# X-Bot.net
KiCad netlist of a schematic drawn in Altium Designer
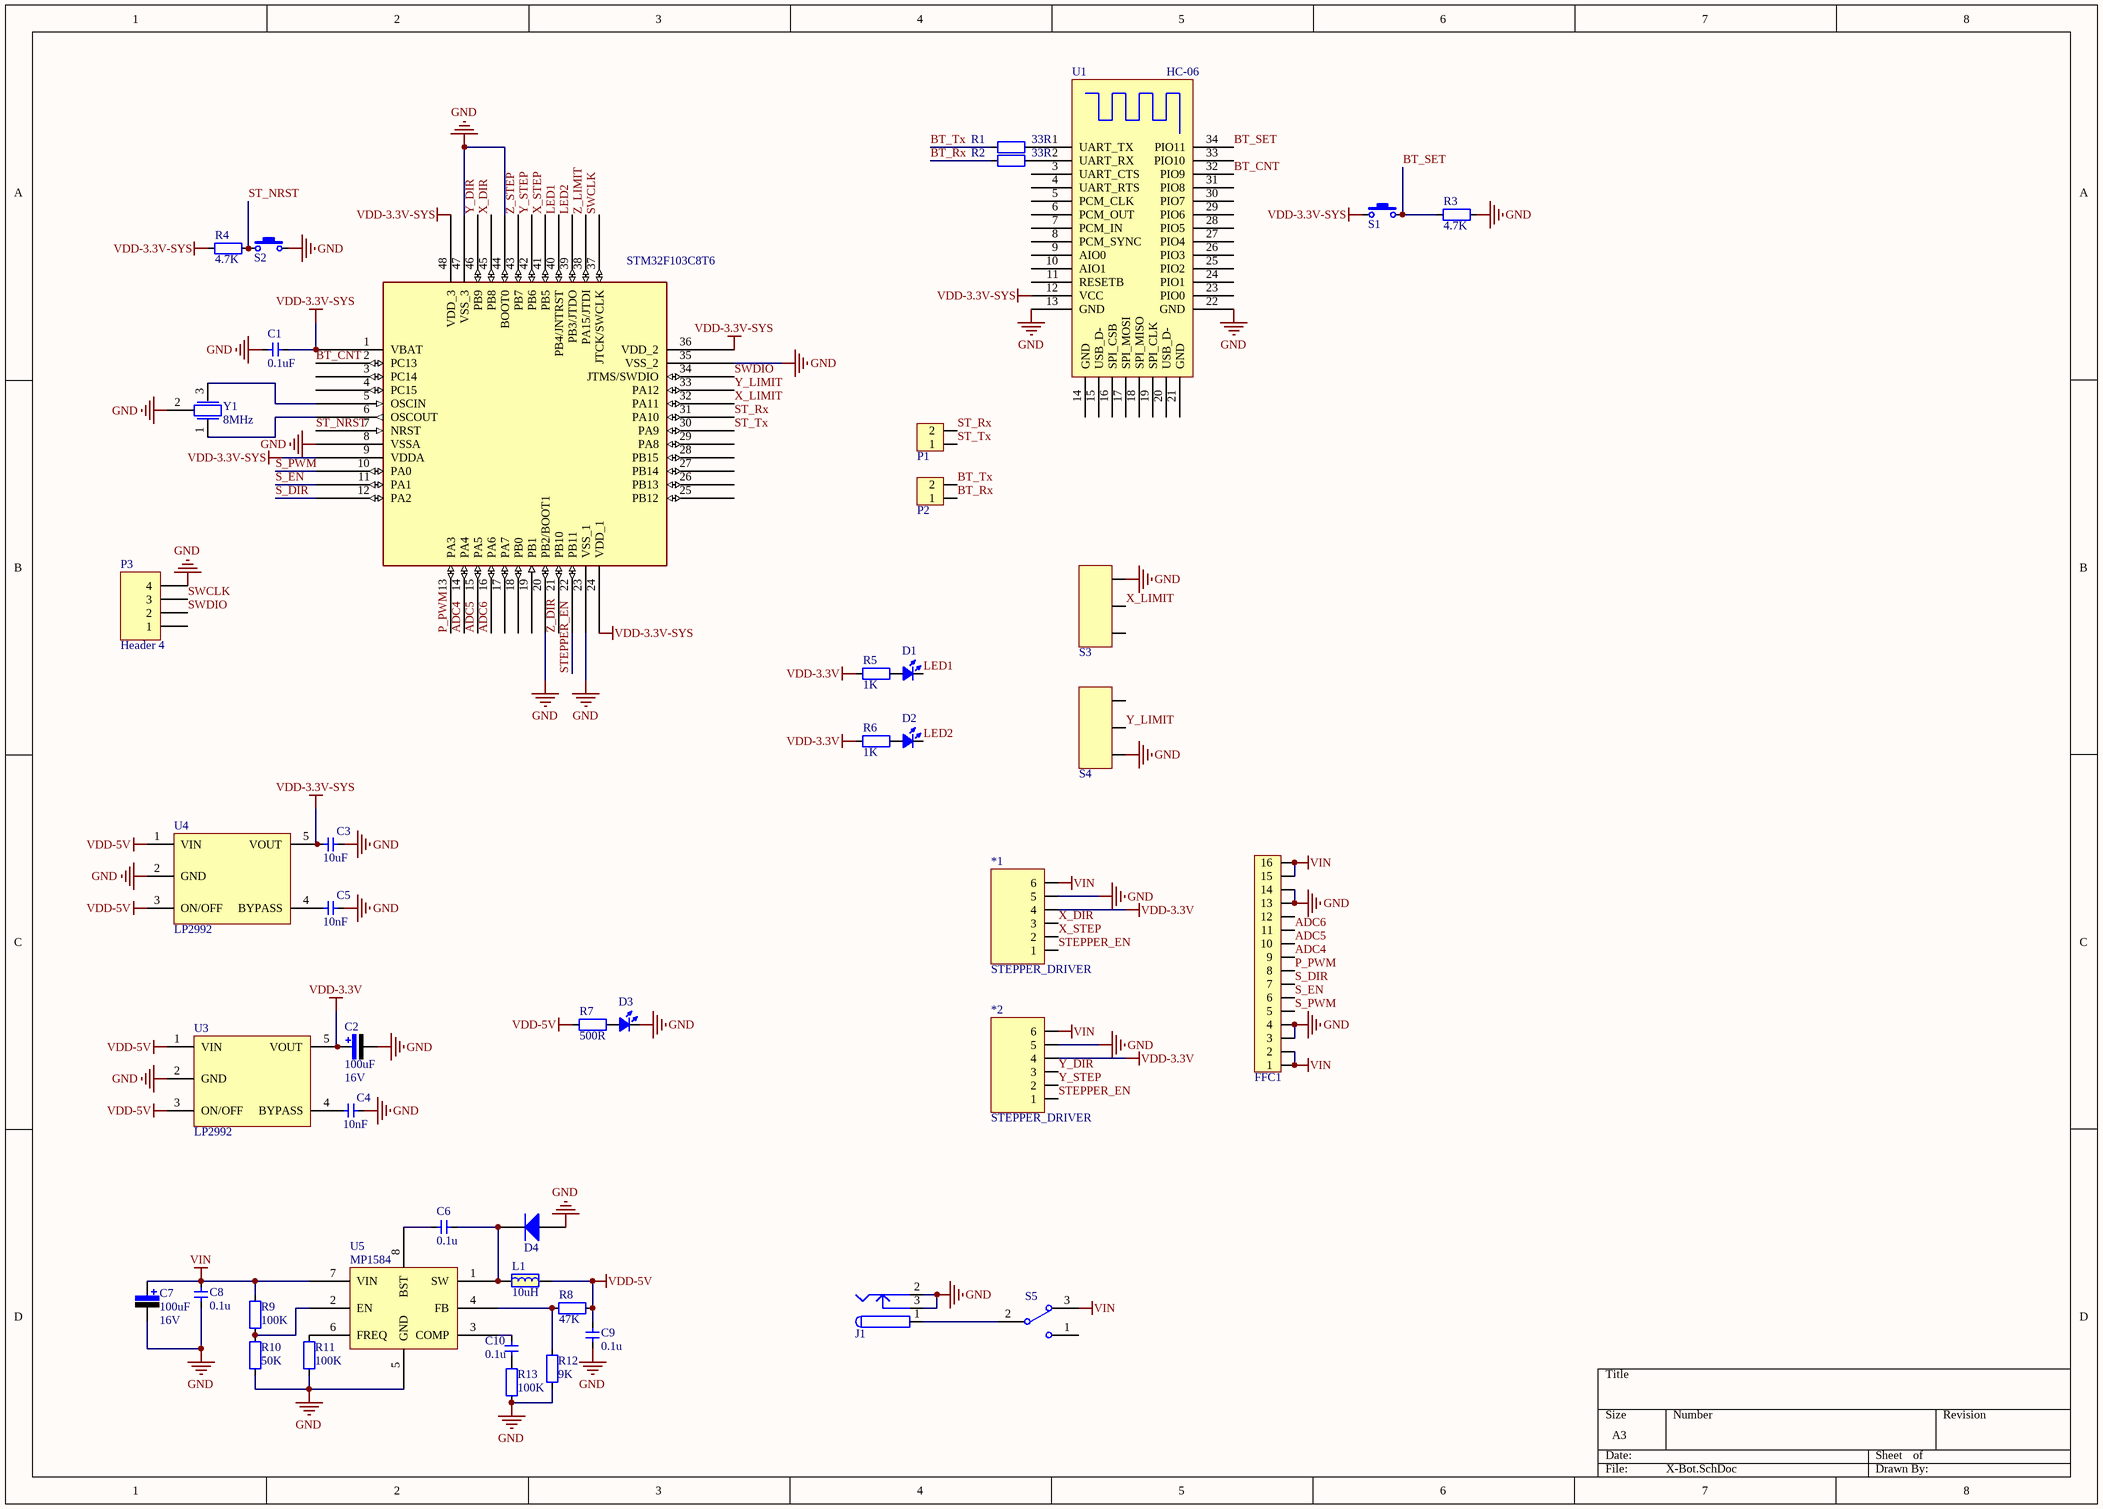
[diagram p0: X-Bot.SchDoc]

(export (version "E")
  (design (tool "Eeschema 10.0.6"))
  (components
    (comp (ref "*1")
      (value "STEPPER_DRIVER")
      (footprint "STEPPER_DRIVER")
      (libsource (lib "mLib") (part "STEPPER_DRIVER"))
    )
    (comp (ref "*2")
      (value "STEPPER_DRIVER")
      (footprint "STEPPER_DRIVER")
      (libsource (lib "mLib") (part "STEPPER_DRIVER"))
    )
    (comp (ref "C1")
      (value "0.1uF")
      (footprint "mLib:0603-CAP")
      (description "Capacitor")
      (libsource (lib "mLib") (part "电容-0603"))
    )
    (comp (ref "C2")
      (value "100uF")
      (footprint "3528-CAP")
      (description "极性电解电容")
      (fields
        (field (name "VOL") "16V")
        (field (name "Comment") "电容 3528")
        (field (name "PUBLISHER") "Altium Limited")
      )
      (libsource (lib "") (part "电容 3528_1"))
    )
    (comp (ref "C3")
      (value "10uF")
      (footprint "mLib:0603-CAP")
      (description "Capacitor")
      (fields (field (name "Comment") "10nF"))
      (libsource (lib "mLib") (part "电容-0603"))
    )
    (comp (ref "C4")
      (value "10nF")
      (footprint "mLib:0603-CAP")
      (description "Capacitor")
      (libsource (lib "mLib") (part "电容-0603"))
    )
    (comp (ref "C5")
      (value "10nF")
      (footprint "mLib:0603-CAP")
      (description "Capacitor")
      (libsource (lib "mLib") (part "电容-0603"))
    )
    (comp (ref "C6")
      (value "0.1u")
      (footprint "mLib:0603-CAP")
      (description "Capacitor")
      (fields (field (name "Comment") "电容-0603"))
      (libsource (lib "mLib") (part "电容-0603"))
    )
    (comp (ref "C7")
      (value "100uF")
      (footprint "3528-CAP")
      (description "极性电解电容")
      (fields
        (field (name "VOL") "16V")
        (field (name "Comment") "电容 3528")
        (field (name "PUBLISHER") "Altium Limited")
      )
      (libsource (lib "mLib") (part "电容 3528"))
    )
    (comp (ref "C8")
      (value "0.1u")
      (footprint "mLib:0603-CAP")
      (description "Capacitor")
      (fields (field (name "Comment") "电容-0603"))
      (libsource (lib "mLib") (part "电容-0603"))
    )
    (comp (ref "C9")
      (value "0.1u")
      (footprint "mLib:0603-CAP")
      (description "Capacitor")
      (fields (field (name "Comment") "电容-0603"))
      (libsource (lib "mLib") (part "电容-0603"))
    )
    (comp (ref "C10")
      (value "0.1u")
      (footprint "mLib:0603-CAP")
      (description "Capacitor")
      (fields (field (name "Comment") "电容-0603"))
      (libsource (lib "mLib") (part "电容-0603"))
    )
    (comp (ref "D1")
      (value "LED-0603")
      (footprint "mLib:0603-LED-BLUE")
      (description "LED")
      (libsource (lib "mLib") (part "LED-0603"))
    )
    (comp (ref "D2")
      (value "LED-0603")
      (footprint "mLib:0603-LED-BLUE")
      (description "LED")
      (libsource (lib "mLib") (part "LED-0603"))
    )
    (comp (ref "D3")
      (value "LED-0603")
      (footprint "mLib:0603-LED-BLUE")
      (description "LED")
      (libsource (lib "mLib") (part "LED-0603"))
    )
    (comp (ref "D4")
      (value "二极管-5819W")
      (footprint "SOD-123")
      (description "40V")
      (libsource (lib "mLib") (part "二极管-5819W"))
    )
    (comp (ref "FFC1")
      (value "FFC_0.5_16")
      (footprint "FFC_0.5_16")
      (description "FFC")
      (libsource (lib "Integrated_Library") (part "FFC_0.5_16"))
    )
    (comp (ref "J1")
      (value "PowerJack_2.5")
      (footprint "KLD_0202")
      (description "DC Power Jack")
      (libsource (lib "Integrated_Library") (part "PowerJack_2.5"))
    )
    (comp (ref "L1")
      (value "10uH")
      (footprint "L-SMD-7")
      (description "磁珠")
      (libsource (lib "mLib") (part "电感-0805"))
    )
    (comp (ref "P1")
      (value "HDR1x2_2.54")
      (footprint "HDR1X2_2.54_180")
      (description "Header")
      (libsource (lib "Integrated_Library") (part "HDR1x2_2.54"))
    )
    (comp (ref "P2")
      (value "HDR1x2_2.54")
      (footprint "HDR1X2_2.54_180")
      (description "Header")
      (libsource (lib "Integrated_Library") (part "HDR1x2_2.54"))
    )
    (comp (ref "P3")
      (value "Header 4")
      (footprint "HDR1X4")
      (description "Header, 4-Pin")
      (fields (field (name "PUBLISHER") "Altium Limited"))
      (libsource (lib "Miscellaneous Connectors") (part "Header 4"))
    )
    (comp (ref "R1")
      (value "33R")
      (footprint "mLib:0603-RES")
      (description "Resistor")
      (fields (field (name "Comment") "500R"))
      (libsource (lib "") (part "电阻-0603_2"))
    )
    (comp (ref "R2")
      (value "33R")
      (footprint "mLib:0603-RES")
      (description "Resistor")
      (fields (field (name "Comment") "500R"))
      (libsource (lib "") (part "电阻-0603_2"))
    )
    (comp (ref "R3")
      (value "4.7K")
      (footprint "mLib:0603-RES")
      (description "Resistor")
      (libsource (lib "mLib") (part "电阻-0603"))
    )
    (comp (ref "R4")
      (value "4.7K")
      (footprint "mLib:0603-RES")
      (description "Resistor")
      (libsource (lib "mLib") (part "电阻-0603"))
    )
    (comp (ref "R5")
      (value "1K")
      (footprint "mLib:0603-RES")
      (description "Resistor")
      (fields (field (name "Comment") "500R"))
      (libsource (lib "") (part "电阻-0603_2"))
    )
    (comp (ref "R6")
      (value "1K")
      (footprint "mLib:0603-RES")
      (description "Resistor")
      (fields (field (name "Comment") "500R"))
      (libsource (lib "") (part "电阻-0603_2"))
    )
    (comp (ref "R7")
      (value "500R")
      (footprint "mLib:0603-RES")
      (description "Resistor")
      (libsource (lib "") (part "电阻-0603_2"))
    )
    (comp (ref "R8")
      (value "47K")
      (footprint "mLib:0603-RES")
      (description "Resistor")
      (fields (field (name "Comment") "100K"))
      (libsource (lib "mLib") (part "电阻-0603"))
    )
    (comp (ref "R9")
      (value "100K")
      (footprint "mLib:0603-RES")
      (description "Resistor")
      (libsource (lib "") (part "电阻-0603_1"))
    )
    (comp (ref "R10")
      (value "50K")
      (footprint "mLib:0603-RES")
      (description "Resistor")
      (fields (field (name "Comment") "100K"))
      (libsource (lib "") (part "电阻-0603_1"))
    )
    (comp (ref "R11")
      (value "100K")
      (footprint "mLib:0603-RES")
      (description "Resistor")
      (libsource (lib "") (part "电阻-0603_1"))
    )
    (comp (ref "R12")
      (value "9K")
      (footprint "mLib:0603-RES")
      (description "Resistor")
      (fields (field (name "Comment") "100K"))
      (libsource (lib "") (part "电阻-0603_1"))
    )
    (comp (ref "R13")
      (value "100K")
      (footprint "mLib:0603-RES")
      (description "Resistor")
      (libsource (lib "") (part "电阻-0603_1"))
    )
    (comp (ref "S1")
      (value "ButtonTACT_3x4x2_180")
      (footprint "ButtonTACT_3x4x2_180H")
      (description "Button")
      (libsource (lib "Integrated_Library") (part "ButtonTACT_3x4x2_180"))
    )
    (comp (ref "S2")
      (value "ButtonTACT_3x4x2_180")
      (footprint "ButtonTACT_3x4x2_180H")
      (description "Button")
      (libsource (lib "Integrated_Library") (part "ButtonTACT_3x4x2_180"))
    )
    (comp (ref "S3")
      (value "LimitSwitch")
      (footprint "Limit Switch")
      (libsource (lib "mLib") (part "LimitSwitch"))
    )
    (comp (ref "S4")
      (value "LimitSwitch")
      (footprint "Limit Switch")
      (libsource (lib "mLib") (part "LimitSwitch"))
    )
    (comp (ref "S5")
      (value "SwitchSPDT_4.3x8.6_D90")
      (footprint "SwitchSPDT_4.3X8.6_D90")
      (description "Switch")
      (libsource (lib "Integrated_Library") (part "SwitchSPDT_4.3x8.6_D90"))
    )
    (comp (ref "U1")
      (value "HC-06")
      (footprint "蓝牙模块HC-06")
      (description "HM bluetooth module HM-01,HM-02,HM-09")
      (libsource (lib "HMSoft") (part "HM01_02_09_1"))
    )
    (comp (ref "U2")
      (value "STM32F103C8T6")
      (footprint "LQFP-48")
      (description "MCU")
      (libsource (lib "mLib") (part "STM32F103C8T6"))
    )
    (comp (ref "U3")
      (value "LP2992")
      (footprint "SOT23-5")
      (description "LDO")
      (libsource (lib "mLib") (part "LP2992"))
    )
    (comp (ref "U4")
      (value "LP2992")
      (footprint "SOT23-5")
      (description "LDO")
      (libsource (lib "mLib") (part "LP2992"))
    )
    (comp (ref "U5")
      (value "MP1584")
      (footprint "SO-8")
      (description "电源芯片")
      (libsource (lib "mLib") (part "MP1584"))
    )
    (comp (ref "Y1")
      (value "8MHz")
      (footprint "晶振-3P")
      (description "村田贴片")
      (libsource (lib "mLib") (part "晶振-3Pin"))
    )
  )
  (nets
    (net (code "1") (name "/ADC4") (class "Default")
      (node (ref "FFC1") (pin "9") (pinfunction "9_9") (pintype "passive"))
      (node (ref "U2") (pin "14") (pinfunction "PA4_14") (pintype "bidirectional"))
    )
    (net (code "2") (name "/ADC5") (class "Default")
      (node (ref "FFC1") (pin "10") (pinfunction "10_10") (pintype "passive"))
      (node (ref "U2") (pin "15") (pinfunction "PA5_15") (pintype "bidirectional"))
    )
    (net (code "3") (name "/ADC6") (class "Default")
      (node (ref "FFC1") (pin "11") (pinfunction "11_11") (pintype "passive"))
      (node (ref "U2") (pin "16") (pinfunction "PA6_16") (pintype "bidirectional"))
    )
    (net (code "4") (name "/BT_CNT") (class "Default")
      (node (ref "U1") (pin "32") (pinfunction "PIO9_32") (pintype "passive"))
      (node (ref "U2") (pin "2") (pinfunction "PC13_2") (pintype "bidirectional"))
    )
    (net (code "5") (name "/BT_Rx") (class "Default")
      (node (ref "P2") (pin "1") (pinfunction "1_1") (pintype "passive"))
      (node (ref "R2") (pin "1") (pinfunction "1_1") (pintype "passive"))
    )
    (net (code "6") (name "/BT_SET") (class "Default")
      (node (ref "R3") (pin "2") (pinfunction "2_2") (pintype "passive"))
      (node (ref "S1") (pin "2") (pinfunction "2_2") (pintype "passive"))
      (node (ref "U1") (pin "34") (pinfunction "PIO11_34") (pintype "passive"))
    )
    (net (code "7") (name "/BT_Tx") (class "Default")
      (node (ref "P2") (pin "2") (pinfunction "2_2") (pintype "passive"))
      (node (ref "R1") (pin "1") (pinfunction "1_1") (pintype "passive"))
    )
    (net (code "8") (name "/LED1") (class "Default")
      (node (ref "D1") (pin "2") (pinfunction "K_2") (pintype "passive"))
      (node (ref "U2") (pin "40") (pinfunction "PB4/JNTRST_40") (pintype "bidirectional"))
    )
    (net (code "9") (name "/LED2") (class "Default")
      (node (ref "D2") (pin "2") (pinfunction "K_2") (pintype "passive"))
      (node (ref "U2") (pin "39") (pinfunction "PB3/JTDO_39") (pintype "bidirectional"))
    )
    (net (code "10") (name "/P_PWM") (class "Default")
      (node (ref "FFC1") (pin "8") (pinfunction "8_8") (pintype "passive"))
      (node (ref "U2") (pin "13") (pinfunction "PA3_13") (pintype "bidirectional"))
    )
    (net (code "11") (name "/STEPPER_EN") (class "Default")
      (node (ref "*1") (pin "1") (pinfunction "1_1") (pintype "passive"))
      (node (ref "*2") (pin "1") (pinfunction "1_1") (pintype "passive"))
      (node (ref "U2") (pin "22") (pinfunction "PB11_22") (pintype "bidirectional"))
    )
    (net (code "12") (name "/ST_NRST") (class "Default")
      (node (ref "R4") (pin "1") (pinfunction "1_1") (pintype "passive"))
      (node (ref "S2") (pin "1") (pinfunction "1_1") (pintype "passive"))
      (node (ref "U2") (pin "7") (pinfunction "NRST_7") (pintype "input"))
    )
    (net (code "13") (name "/ST_Rx") (class "Default")
      (node (ref "P1") (pin "2") (pinfunction "2_2") (pintype "passive"))
      (node (ref "U2") (pin "31") (pinfunction "PA10_31") (pintype "bidirectional"))
    )
    (net (code "14") (name "/ST_Tx") (class "Default")
      (node (ref "P1") (pin "1") (pinfunction "1_1") (pintype "passive"))
      (node (ref "U2") (pin "30") (pinfunction "PA9_30") (pintype "bidirectional"))
    )
    (net (code "15") (name "/SWCLK") (class "Default")
      (node (ref "P3") (pin "3") (pinfunction "3_3") (pintype "passive"))
      (node (ref "U2") (pin "37") (pinfunction "JTCK/SWCLK_37") (pintype "bidirectional"))
    )
    (net (code "16") (name "/SWDIO") (class "Default")
      (node (ref "P3") (pin "2") (pinfunction "2_2") (pintype "passive"))
      (node (ref "U2") (pin "34") (pinfunction "JTMS/SWDIO_34") (pintype "bidirectional"))
    )
    (net (code "17") (name "/S_DIR") (class "Default")
      (node (ref "FFC1") (pin "7") (pinfunction "7_7") (pintype "passive"))
      (node (ref "U2") (pin "12") (pinfunction "PA2_12") (pintype "bidirectional"))
    )
    (net (code "18") (name "/S_EN") (class "Default")
      (node (ref "FFC1") (pin "6") (pinfunction "6_6") (pintype "passive"))
      (node (ref "U2") (pin "11") (pinfunction "PA1_11") (pintype "bidirectional"))
    )
    (net (code "19") (name "/S_PWM") (class "Default")
      (node (ref "FFC1") (pin "5") (pinfunction "5_5") (pintype "passive"))
      (node (ref "U2") (pin "10") (pinfunction "PA0_10") (pintype "bidirectional"))
    )
    (net (code "20") (name "/X_DIR") (class "Default")
      (node (ref "*1") (pin "3") (pinfunction "3_3") (pintype "passive"))
      (node (ref "U2") (pin "45") (pinfunction "PB8_45") (pintype "bidirectional"))
    )
    (net (code "21") (name "/X_LIMIT") (class "Default")
      (node (ref "S3") (pin "2") (pintype "power_in"))
      (node (ref "U2") (pin "32") (pinfunction "PA11_32") (pintype "bidirectional"))
    )
    (net (code "22") (name "/X_STEP") (class "Default")
      (node (ref "*1") (pin "2") (pinfunction "2_2") (pintype "passive"))
      (node (ref "U2") (pin "41") (pinfunction "PB5_41") (pintype "bidirectional"))
    )
    (net (code "23") (name "/Y_DIR") (class "Default")
      (node (ref "*2") (pin "3") (pinfunction "3_3") (pintype "passive"))
      (node (ref "U2") (pin "46") (pinfunction "PB9_46") (pintype "bidirectional"))
    )
    (net (code "24") (name "/Y_LIMIT") (class "Default")
      (node (ref "S4") (pin "2") (pintype "power_in"))
      (node (ref "U2") (pin "33") (pinfunction "PA12_33") (pintype "bidirectional"))
    )
    (net (code "25") (name "/Y_STEP") (class "Default")
      (node (ref "*2") (pin "2") (pinfunction "2_2") (pintype "passive"))
      (node (ref "U2") (pin "42") (pinfunction "PB6_42") (pintype "bidirectional"))
    )
    (net (code "26") (name "/Z_DIR") (class "Default")
      (node (ref "U2") (pin "21") (pinfunction "PB10_21") (pintype "bidirectional"))
    )
    (net (code "27") (name "/Z_LIMIT") (class "Default")
      (node (ref "U2") (pin "38") (pinfunction "PA15/JTDI_38") (pintype "bidirectional"))
    )
    (net (code "28") (name "/Z_STEP") (class "Default")
      (node (ref "U2") (pin "43") (pinfunction "PB7_43") (pintype "bidirectional"))
    )
    (net (code "29") (name "GND") (class "Default")
      (node (ref "*1") (pin "5") (pinfunction "5_5") (pintype "passive"))
      (node (ref "*2") (pin "5") (pinfunction "5_5") (pintype "passive"))
      (node (ref "C1") (pin "1") (pinfunction "1_1") (pintype "passive"))
      (node (ref "C2") (pin "2") (pinfunction "2_2") (pintype "passive"))
      (node (ref "C3") (pin "1") (pinfunction "1_1") (pintype "passive"))
      (node (ref "C4") (pin "1") (pinfunction "1_1") (pintype "passive"))
      (node (ref "C5") (pin "1") (pinfunction "1_1") (pintype "passive"))
      (node (ref "C7") (pin "2") (pinfunction "2_2") (pintype "passive"))
      (node (ref "C8") (pin "1") (pinfunction "1_1") (pintype "passive"))
      (node (ref "C9") (pin "2") (pinfunction "2_2") (pintype "passive"))
      (node (ref "D3") (pin "2") (pinfunction "K_2") (pintype "passive"))
      (node (ref "D4") (pin "1") (pinfunction "A_1") (pintype "passive"))
      (node (ref "FFC1") (pin "13") (pinfunction "13_13") (pintype "passive"))
      (node (ref "FFC1") (pin "14") (pinfunction "14_14") (pintype "passive"))
      (node (ref "FFC1") (pin "3") (pinfunction "3_3") (pintype "passive"))
      (node (ref "FFC1") (pin "4") (pinfunction "4_4") (pintype "passive"))
      (node (ref "J1") (pin "2") (pinfunction "2_2") (pintype "power_in"))
      (node (ref "J1") (pin "3") (pinfunction "3_3") (pintype "power_in"))
      (node (ref "P3") (pin "4") (pinfunction "4_4") (pintype "passive"))
      (node (ref "R10") (pin "1") (pinfunction "1_1") (pintype "passive"))
      (node (ref "R11") (pin "1") (pinfunction "1_1") (pintype "passive"))
      (node (ref "R12") (pin "1") (pinfunction "1_1") (pintype "passive"))
      (node (ref "R13") (pin "1") (pinfunction "1_1") (pintype "passive"))
      (node (ref "R3") (pin "1") (pinfunction "1_1") (pintype "passive"))
      (node (ref "S2") (pin "2") (pinfunction "2_2") (pintype "passive"))
      (node (ref "S3") (pin "3") (pintype "power_in"))
      (node (ref "S4") (pin "1") (pintype "power_in"))
      (node (ref "U1") (pin "13") (pinfunction "GND_13") (pintype "passive"))
      (node (ref "U1") (pin "22") (pinfunction "GND_22") (pintype "passive"))
      (node (ref "U2") (pin "20") (pinfunction "PB2/BOOT1_20") (pintype "bidirectional"))
      (node (ref "U2") (pin "23") (pinfunction "VSS_1_23") (pintype "power_in"))
      (node (ref "U2") (pin "35") (pinfunction "VSS_2_35") (pintype "power_in"))
      (node (ref "U2") (pin "44") (pinfunction "BOOT0_44") (pintype "bidirectional"))
      (node (ref "U2") (pin "47") (pinfunction "VSS_3_47") (pintype "power_in"))
      (node (ref "U2") (pin "8") (pinfunction "VSSA_8") (pintype "power_in"))
      (node (ref "U3") (pin "2") (pinfunction "GND_2") (pintype "passive"))
      (node (ref "U4") (pin "2") (pinfunction "GND_2") (pintype "passive"))
      (node (ref "U5") (pin "5") (pinfunction "GND_5") (pintype "passive"))
      (node (ref "Y1") (pin "2") (pinfunction "2_2") (pintype "passive"))
    )
    (net (code "30") (name "Net-(C10-Pad1)") (class "Default")
      (node (ref "C10") (pin "1") (pinfunction "1_1") (pintype "passive"))
      (node (ref "R13") (pin "2") (pinfunction "2_2") (pintype "passive"))
    )
    (net (code "31") (name "Net-(D1-A)") (class "Default")
      (node (ref "D1") (pin "1") (pinfunction "A_1") (pintype "passive"))
      (node (ref "R5") (pin "2") (pinfunction "2_2") (pintype "passive"))
    )
    (net (code "32") (name "Net-(D2-A)") (class "Default")
      (node (ref "D2") (pin "1") (pinfunction "A_1") (pintype "passive"))
      (node (ref "R6") (pin "2") (pinfunction "2_2") (pintype "passive"))
    )
    (net (code "33") (name "Net-(D3-A)") (class "Default")
      (node (ref "D3") (pin "1") (pinfunction "A_1") (pintype "passive"))
      (node (ref "R7") (pin "2") (pinfunction "2_2") (pintype "passive"))
    )
    (net (code "34") (name "Net-(D4-K)") (class "Default")
      (node (ref "C6") (pin "2") (pinfunction "2_2") (pintype "passive"))
      (node (ref "D4") (pin "2") (pinfunction "K_2") (pintype "passive"))
      (node (ref "L1") (pin "1") (pintype "passive"))
      (node (ref "U5") (pin "1") (pinfunction "SW_1") (pintype "passive"))
    )
    (net (code "35") (name "Net-(J1-Pad1)") (class "Default")
      (node (ref "J1") (pin "1") (pinfunction "1_1") (pintype "power_in"))
      (node (ref "S5") (pin "2") (pinfunction "2_2") (pintype "passive"))
    )
    (net (code "36") (name "Net-(U1-UART_RX)") (class "Default")
      (node (ref "R2") (pin "2") (pinfunction "2_2") (pintype "passive"))
      (node (ref "U1") (pin "2") (pinfunction "UART_RX_2") (pintype "passive"))
    )
    (net (code "37") (name "Net-(U1-UART_TX)") (class "Default")
      (node (ref "R1") (pin "2") (pinfunction "2_2") (pintype "passive"))
      (node (ref "U1") (pin "1") (pinfunction "UART_TX_1") (pintype "passive"))
    )
    (net (code "38") (name "Net-(U2-OSCIN)") (class "Default")
      (node (ref "U2") (pin "5") (pinfunction "OSCIN_5") (pintype "input"))
      (node (ref "Y1") (pin "3") (pinfunction "3_3") (pintype "passive"))
    )
    (net (code "39") (name "Net-(U2-OSCOUT)") (class "Default")
      (node (ref "U2") (pin "6") (pinfunction "OSCOUT_6") (pintype "output"))
      (node (ref "Y1") (pin "1") (pinfunction "1_1") (pintype "passive"))
    )
    (net (code "40") (name "Net-(U3-BYPASS)") (class "Default")
      (node (ref "C4") (pin "2") (pinfunction "2_2") (pintype "passive"))
      (node (ref "U3") (pin "4") (pinfunction "BYPASS_4") (pintype "passive"))
    )
    (net (code "41") (name "Net-(U4-BYPASS)") (class "Default")
      (node (ref "C5") (pin "2") (pinfunction "2_2") (pintype "passive"))
      (node (ref "U4") (pin "4") (pinfunction "BYPASS_4") (pintype "passive"))
    )
    (net (code "42") (name "Net-(U5-BST)") (class "Default")
      (node (ref "C6") (pin "1") (pinfunction "1_1") (pintype "passive"))
      (node (ref "U5") (pin "8") (pinfunction "BST_8") (pintype "passive"))
    )
    (net (code "43") (name "Net-(U5-COMP)") (class "Default")
      (node (ref "C10") (pin "2") (pinfunction "2_2") (pintype "passive"))
      (node (ref "U5") (pin "3") (pinfunction "COMP_3") (pintype "passive"))
    )
    (net (code "44") (name "Net-(U5-EN)") (class "Default")
      (node (ref "R10") (pin "2") (pinfunction "2_2") (pintype "passive"))
      (node (ref "R9") (pin "1") (pinfunction "1_1") (pintype "passive"))
      (node (ref "U5") (pin "2") (pinfunction "EN_2") (pintype "passive"))
    )
    (net (code "45") (name "Net-(U5-FB)") (class "Default")
      (node (ref "R12") (pin "2") (pinfunction "2_2") (pintype "passive"))
      (node (ref "R8") (pin "2") (pinfunction "2_2") (pintype "passive"))
      (node (ref "U5") (pin "4") (pinfunction "FB_4") (pintype "passive"))
    )
    (net (code "46") (name "Net-(U5-FREQ)") (class "Default")
      (node (ref "R11") (pin "2") (pinfunction "2_2") (pintype "passive"))
      (node (ref "U5") (pin "6") (pinfunction "FREQ_6") (pintype "passive"))
    )
    (net (code "47") (name "VDD-3.3V") (class "Default")
      (node (ref "*1") (pin "4") (pinfunction "4_4") (pintype "passive"))
      (node (ref "*2") (pin "4") (pinfunction "4_4") (pintype "passive"))
      (node (ref "C2") (pin "1") (pinfunction "1_1") (pintype "passive"))
      (node (ref "R5") (pin "1") (pinfunction "1_1") (pintype "passive"))
      (node (ref "R6") (pin "1") (pinfunction "1_1") (pintype "passive"))
      (node (ref "U3") (pin "5") (pinfunction "VOUT_5") (pintype "passive"))
    )
    (net (code "48") (name "VDD-3.3V-SYS") (class "Default")
      (node (ref "C1") (pin "2") (pinfunction "2_2") (pintype "passive"))
      (node (ref "C3") (pin "2") (pinfunction "2_2") (pintype "passive"))
      (node (ref "R4") (pin "2") (pinfunction "2_2") (pintype "passive"))
      (node (ref "S1") (pin "1") (pinfunction "1_1") (pintype "passive"))
      (node (ref "U1") (pin "12") (pinfunction "VCC_12") (pintype "passive"))
      (node (ref "U2") (pin "1") (pinfunction "VBAT_1") (pintype "power_in"))
      (node (ref "U2") (pin "24") (pinfunction "VDD_1_24") (pintype "power_in"))
      (node (ref "U2") (pin "36") (pinfunction "VDD_2_36") (pintype "power_in"))
      (node (ref "U2") (pin "48") (pinfunction "VDD_3_48") (pintype "power_in"))
      (node (ref "U2") (pin "9") (pinfunction "VDDA_9") (pintype "power_in"))
      (node (ref "U4") (pin "5") (pinfunction "VOUT_5") (pintype "passive"))
    )
    (net (code "49") (name "VDD-5V") (class "Default")
      (node (ref "C9") (pin "1") (pinfunction "1_1") (pintype "passive"))
      (node (ref "L1") (pin "2") (pinfunction "2_2") (pintype "passive"))
      (node (ref "R7") (pin "1") (pinfunction "1_1") (pintype "passive"))
      (node (ref "R8") (pin "1") (pinfunction "1_1") (pintype "passive"))
      (node (ref "U3") (pin "1") (pinfunction "VIN_1") (pintype "passive"))
      (node (ref "U3") (pin "3") (pinfunction "ON/OFF_3") (pintype "passive"))
      (node (ref "U4") (pin "1") (pinfunction "VIN_1") (pintype "passive"))
      (node (ref "U4") (pin "3") (pinfunction "ON/OFF_3") (pintype "passive"))
    )
    (net (code "50") (name "VIN") (class "Default")
      (node (ref "*1") (pin "6") (pinfunction "6_6") (pintype "passive"))
      (node (ref "*2") (pin "6") (pinfunction "6_6") (pintype "passive"))
      (node (ref "C7") (pin "1") (pinfunction "1_1") (pintype "passive"))
      (node (ref "C8") (pin "2") (pinfunction "2_2") (pintype "passive"))
      (node (ref "FFC1") (pin "1") (pinfunction "1_1") (pintype "passive"))
      (node (ref "FFC1") (pin "15") (pinfunction "15_15") (pintype "passive"))
      (node (ref "FFC1") (pin "16") (pinfunction "16_16") (pintype "passive"))
      (node (ref "FFC1") (pin "2") (pinfunction "2_2") (pintype "passive"))
      (node (ref "R9") (pin "2") (pinfunction "2_2") (pintype "passive"))
      (node (ref "S5") (pin "3") (pinfunction "3_3") (pintype "passive"))
      (node (ref "U5") (pin "7") (pinfunction "VIN_7") (pintype "passive"))
    )
    (net (code "51") (name "unconnected-(FFC1-Pad12)") (class "Default")
      (node (ref "FFC1") (pin "12") (pinfunction "12_12") (pintype "passive"))
    )
    (net (code "52") (name "unconnected-(P3-Pad1)") (class "Default")
      (node (ref "P3") (pin "1") (pinfunction "1_1") (pintype "passive"))
    )
    (net (code "53") (name "unconnected-(S3-Pad1)") (class "Default")
      (node (ref "S3") (pin "1") (pintype "power_in"))
    )
    (net (code "54") (name "unconnected-(S4-Pad3)") (class "Default")
      (node (ref "S4") (pin "3") (pintype "power_in"))
    )
    (net (code "55") (name "unconnected-(S5-Pad1)") (class "Default")
      (node (ref "S5") (pin "1") (pinfunction "1_1") (pintype "passive"))
    )
    (net (code "56") (name "unconnected-(U1-AIO0-Pad9)") (class "Default")
      (node (ref "U1") (pin "9") (pinfunction "AIO0_9") (pintype "passive"))
    )
    (net (code "57") (name "unconnected-(U1-AIO1-Pad10)") (class "Default")
      (node (ref "U1") (pin "10") (pinfunction "AIO1_10") (pintype "passive"))
    )
    (net (code "58") (name "unconnected-(U1-GND-Pad14)") (class "Default")
      (node (ref "U1") (pin "14") (pinfunction "GND_14") (pintype "passive"))
    )
    (net (code "59") (name "unconnected-(U1-GND-Pad21)") (class "Default")
      (node (ref "U1") (pin "21") (pinfunction "GND_21") (pintype "passive"))
    )
    (net (code "60") (name "unconnected-(U1-PCM_CLK-Pad5)") (class "Default")
      (node (ref "U1") (pin "5") (pinfunction "PCM_CLK_5") (pintype "passive"))
    )
    (net (code "61") (name "unconnected-(U1-PCM_IN-Pad7)") (class "Default")
      (node (ref "U1") (pin "7") (pinfunction "PCM_IN_7") (pintype "passive"))
    )
    (net (code "62") (name "unconnected-(U1-PCM_OUT-Pad6)") (class "Default")
      (node (ref "U1") (pin "6") (pinfunction "PCM_OUT_6") (pintype "passive"))
    )
    (net (code "63") (name "unconnected-(U1-PCM_SYNC-Pad8)") (class "Default")
      (node (ref "U1") (pin "8") (pinfunction "PCM_SYNC_8") (pintype "passive"))
    )
    (net (code "64") (name "unconnected-(U1-PIO0-Pad23)") (class "Default")
      (node (ref "U1") (pin "23") (pinfunction "PIO0_23") (pintype "passive"))
    )
    (net (code "65") (name "unconnected-(U1-PIO1-Pad24)") (class "Default")
      (node (ref "U1") (pin "24") (pinfunction "PIO1_24") (pintype "passive"))
    )
    (net (code "66") (name "unconnected-(U1-PIO2-Pad25)") (class "Default")
      (node (ref "U1") (pin "25") (pinfunction "PIO2_25") (pintype "passive"))
    )
    (net (code "67") (name "unconnected-(U1-PIO3-Pad26)") (class "Default")
      (node (ref "U1") (pin "26") (pinfunction "PIO3_26") (pintype "passive"))
    )
    (net (code "68") (name "unconnected-(U1-PIO4-Pad27)") (class "Default")
      (node (ref "U1") (pin "27") (pinfunction "PIO4_27") (pintype "passive"))
    )
    (net (code "69") (name "unconnected-(U1-PIO5-Pad28)") (class "Default")
      (node (ref "U1") (pin "28") (pinfunction "PIO5_28") (pintype "passive"))
    )
    (net (code "70") (name "unconnected-(U1-PIO6-Pad29)") (class "Default")
      (node (ref "U1") (pin "29") (pinfunction "PIO6_29") (pintype "passive"))
    )
    (net (code "71") (name "unconnected-(U1-PIO7-Pad30)") (class "Default")
      (node (ref "U1") (pin "30") (pinfunction "PIO7_30") (pintype "passive"))
    )
    (net (code "72") (name "unconnected-(U1-PIO8-Pad31)") (class "Default")
      (node (ref "U1") (pin "31") (pinfunction "PIO8_31") (pintype "passive"))
    )
    (net (code "73") (name "unconnected-(U1-PIO10-Pad33)") (class "Default")
      (node (ref "U1") (pin "33") (pinfunction "PIO10_33") (pintype "passive"))
    )
    (net (code "74") (name "unconnected-(U1-RESETB-Pad11)") (class "Default")
      (node (ref "U1") (pin "11") (pinfunction "RESETB_11") (pintype "passive"))
    )
    (net (code "75") (name "unconnected-(U1-SPI_CLK-Pad19)") (class "Default")
      (node (ref "U1") (pin "19") (pinfunction "SPI_CLK_19") (pintype "passive"))
    )
    (net (code "76") (name "unconnected-(U1-SPI_CSB-Pad16)") (class "Default")
      (node (ref "U1") (pin "16") (pinfunction "SPI_CSB_16") (pintype "passive"))
    )
    (net (code "77") (name "unconnected-(U1-SPI_MISO-Pad18)") (class "Default")
      (node (ref "U1") (pin "18") (pinfunction "SPI_MISO_18") (pintype "passive"))
    )
    (net (code "78") (name "unconnected-(U1-SPI_MOSI-Pad17)") (class "Default")
      (node (ref "U1") (pin "17") (pinfunction "SPI_MOSI_17") (pintype "passive"))
    )
    (net (code "79") (name "unconnected-(U1-UART_CTS-Pad3)") (class "Default")
      (node (ref "U1") (pin "3") (pinfunction "UART_CTS_3") (pintype "passive"))
    )
    (net (code "80") (name "unconnected-(U1-UART_RTS-Pad4)") (class "Default")
      (node (ref "U1") (pin "4") (pinfunction "UART_RTS_4") (pintype "passive"))
    )
    (net (code "81") (name "unconnected-(U1-USB_D--Pad15)") (class "Default")
      (node (ref "U1") (pin "15") (pinfunction "USB_D-_15") (pintype "passive"))
    )
    (net (code "82") (name "unconnected-(U1-USB_D--Pad20)") (class "Default")
      (node (ref "U1") (pin "20") (pinfunction "USB_D-_20") (pintype "passive"))
    )
    (net (code "83") (name "unconnected-(U2-PA7-Pad17)") (class "Default")
      (node (ref "U2") (pin "17") (pinfunction "PA7_17") (pintype "bidirectional"))
    )
    (net (code "84") (name "unconnected-(U2-PA8-Pad29)") (class "Default")
      (node (ref "U2") (pin "29") (pinfunction "PA8_29") (pintype "bidirectional"))
    )
    (net (code "85") (name "unconnected-(U2-PB0-Pad18)") (class "Default")
      (node (ref "U2") (pin "18") (pinfunction "PB0_18") (pintype "bidirectional"))
    )
    (net (code "86") (name "unconnected-(U2-PB1-Pad19)") (class "Default")
      (node (ref "U2") (pin "19") (pinfunction "PB1_19") (pintype "input"))
    )
    (net (code "87") (name "unconnected-(U2-PB12-Pad25)") (class "Default")
      (node (ref "U2") (pin "25") (pinfunction "PB12_25") (pintype "bidirectional"))
    )
    (net (code "88") (name "unconnected-(U2-PB13-Pad26)") (class "Default")
      (node (ref "U2") (pin "26") (pinfunction "PB13_26") (pintype "bidirectional"))
    )
    (net (code "89") (name "unconnected-(U2-PB14-Pad27)") (class "Default")
      (node (ref "U2") (pin "27") (pinfunction "PB14_27") (pintype "bidirectional"))
    )
    (net (code "90") (name "unconnected-(U2-PB15-Pad28)") (class "Default")
      (node (ref "U2") (pin "28") (pinfunction "PB15_28") (pintype "bidirectional"))
    )
    (net (code "91") (name "unconnected-(U2-PC14-Pad3)") (class "Default")
      (node (ref "U2") (pin "3") (pinfunction "PC14_3") (pintype "bidirectional"))
    )
    (net (code "92") (name "unconnected-(U2-PC15-Pad4)") (class "Default")
      (node (ref "U2") (pin "4") (pinfunction "PC15_4") (pintype "bidirectional"))
    )
  )
)
